# BV100011_ControlPower.net
KiCad netlist of a schematic drawn in Altium Designer
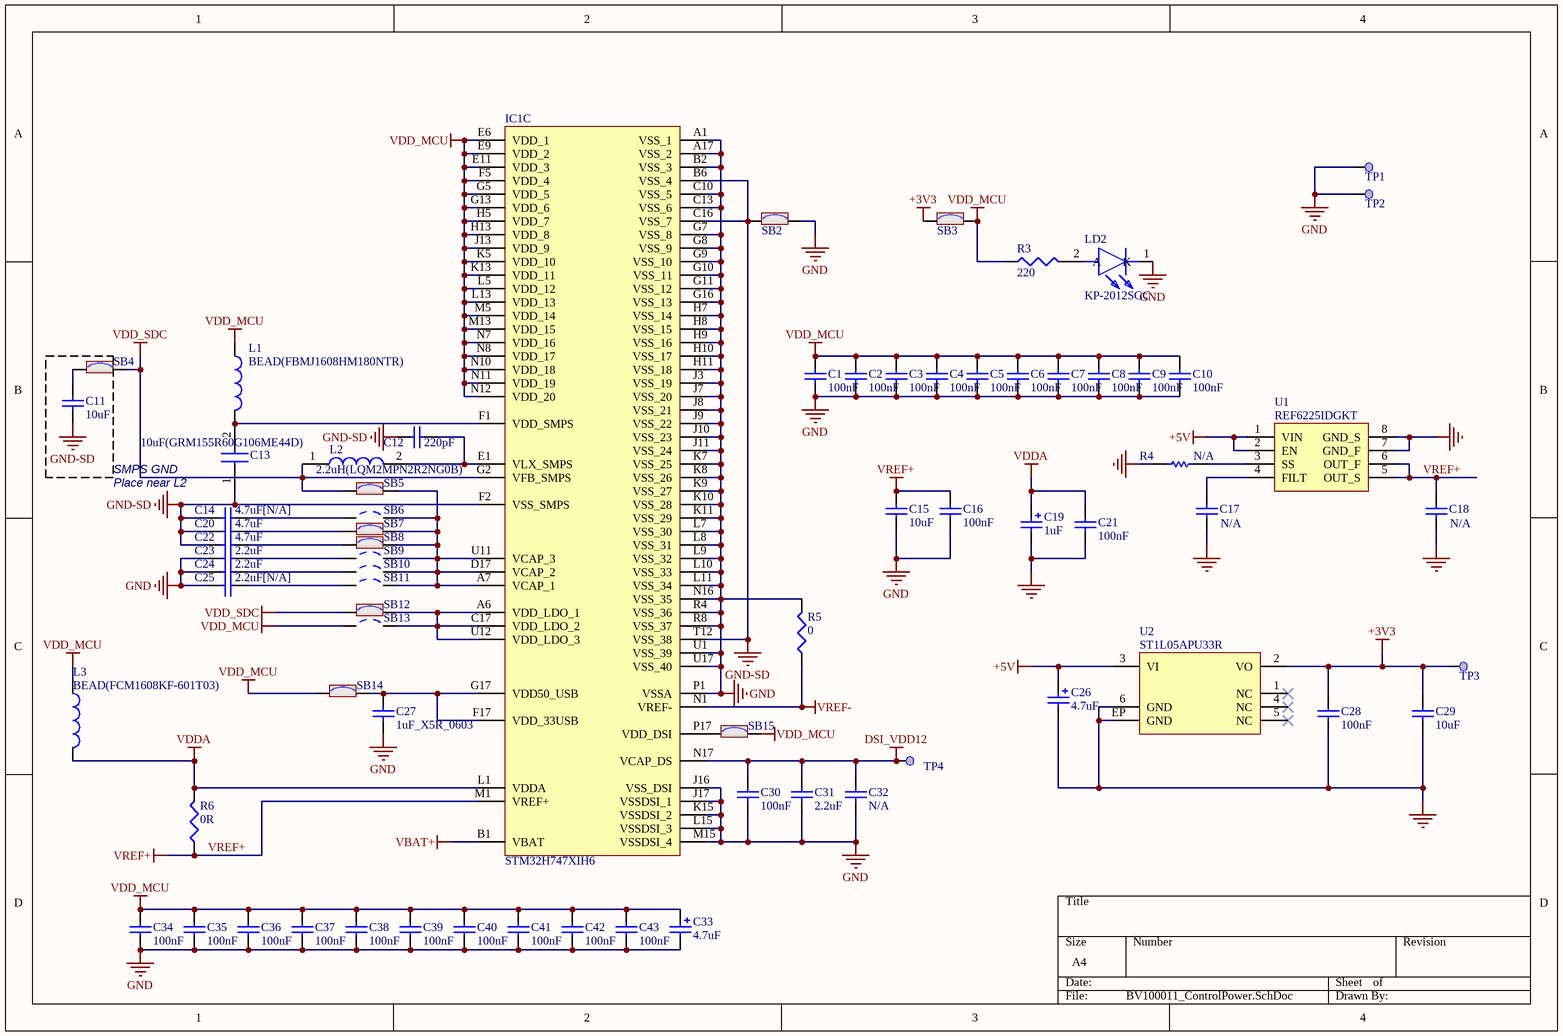
[diagram p0: BV100011_ControlPower.SchDoc]

(export (version "E")
  (design (tool "Eeschema 10.0.6"))
  (components
    (comp (ref "C1")
      (value "100nF")
      (footprint "C0402")
      (description "Capacitor (Semiconductor SIM Model)")
      (fields (field (name "PUBLISHER") "Altium Limited"))
      (libsource (lib "Miscellaneous Devices") (part "Cap Semi"))
    )
    (comp (ref "C2")
      (value "100nF")
      (footprint "C0402")
      (description "Capacitor (Semiconductor SIM Model)")
      (fields (field (name "PUBLISHER") "Altium Limited"))
      (libsource (lib "Miscellaneous Devices") (part "Cap Semi"))
    )
    (comp (ref "C3")
      (value "100nF")
      (footprint "C0402")
      (description "Capacitor (Semiconductor SIM Model)")
      (fields (field (name "PUBLISHER") "Altium Limited"))
      (libsource (lib "Miscellaneous Devices") (part "Cap Semi"))
    )
    (comp (ref "C4")
      (value "100nF")
      (footprint "C0402")
      (description "Capacitor (Semiconductor SIM Model)")
      (fields (field (name "PUBLISHER") "Altium Limited"))
      (libsource (lib "Miscellaneous Devices") (part "Cap Semi"))
    )
    (comp (ref "C5")
      (value "100nF")
      (footprint "C0402")
      (description "Capacitor (Semiconductor SIM Model)")
      (fields (field (name "PUBLISHER") "Altium Limited"))
      (libsource (lib "Miscellaneous Devices") (part "Cap Semi"))
    )
    (comp (ref "C6")
      (value "100nF")
      (footprint "C0402")
      (description "Capacitor (Semiconductor SIM Model)")
      (fields (field (name "PUBLISHER") "Altium Limited"))
      (libsource (lib "Miscellaneous Devices") (part "Cap Semi"))
    )
    (comp (ref "C7")
      (value "100nF")
      (footprint "C0402")
      (description "Capacitor (Semiconductor SIM Model)")
      (fields (field (name "PUBLISHER") "Altium Limited"))
      (libsource (lib "Miscellaneous Devices") (part "Cap Semi"))
    )
    (comp (ref "C8")
      (value "100nF")
      (footprint "C0402")
      (description "Capacitor (Semiconductor SIM Model)")
      (fields (field (name "PUBLISHER") "Altium Limited"))
      (libsource (lib "Miscellaneous Devices") (part "Cap Semi"))
    )
    (comp (ref "C9")
      (value "100nF")
      (footprint "C0402")
      (description "Capacitor (Semiconductor SIM Model)")
      (fields (field (name "PUBLISHER") "Altium Limited"))
      (libsource (lib "Miscellaneous Devices") (part "Cap Semi"))
    )
    (comp (ref "C10")
      (value "100nF")
      (footprint "C0402")
      (description "Capacitor (Semiconductor SIM Model)")
      (fields (field (name "PUBLISHER") "Altium Limited"))
      (libsource (lib "Miscellaneous Devices") (part "Cap Semi"))
    )
    (comp (ref "C11")
      (value "10uF")
      (footprint "C0603")
      (description "Capacitor (Semiconductor SIM Model)")
      (fields (field (name "PUBLISHER") "Altium Limited"))
      (libsource (lib "Miscellaneous Devices") (part "Cap Semi"))
    )
    (comp (ref "C12")
      (value "220pF")
      (footprint "C0402")
      (description "Capacitor (Semiconductor SIM Model)")
      (fields (field (name "PUBLISHER") "Altium Limited"))
      (libsource (lib "Miscellaneous Devices") (part "Cap Semi"))
    )
    (comp (ref "C13")
      (value "10uF(GRM155R60G106ME44D)")
      (footprint "C0402")
      (description "Capacitor")
      (fields
        (field (name "MANUFACTURER_PART_NUMBER") "GRM155R60G106ME44D")
        (field (name "MOUSER PART NUMBER") "81-GRM155R60G106ME4D")
      )
      (libsource (lib "*") (part "GRM155R60G106ME44D"))
    )
    (comp (ref "C14")
      (value "4.7uF[N/A]")
      (footprint "C0402")
      (description "Capacitor (Semiconductor SIM Model)")
      (fields (field (name "PUBLISHER") "Altium Limited"))
      (libsource (lib "Miscellaneous Devices") (part "Cap Semi"))
    )
    (comp (ref "C15")
      (value "10uF")
      (footprint "C0805")
      (description "Capacitor, MLCC, 10uF, 25V, X5R, 10%, 0805, T=0,85mm")
      (fields
        (field (name "INTERNAL_PART_NUMBER") "MCD-00014")
        (field (name "MANUFACTURER_PART_NUMBER") "CC0805KRX5R8BB106")
        (field (name "PROVIDED_BY") "Subcon")
      )
      (libsource (lib "MCD_PARTS_database") (part "Capacitor"))
    )
    (comp (ref "C16")
      (value "100nF")
      (footprint "C0402")
      (description "Capacitor (Semiconductor SIM Model)")
      (fields (field (name "PUBLISHER") "Altium Limited"))
      (libsource (lib "Miscellaneous Devices") (part "Cap Semi"))
    )
    (comp (ref "C17")
      (value "N/A")
      (footprint "C0603")
      (description "Capacitor, MLCC, 1uF, 16V, X5R, 10%, 0603, T=0,8mm")
      (fields
        (field (name "INTERNAL_PART_NUMBER") "MCD-00010")
        (field (name "MANUFACTURER_PART_NUMBER") "CC0603KRX5R7BB105")
        (field (name "PROVIDED_BY") "Subcon")
      )
      (libsource (lib "MCD_PARTS_database") (part "Capacitor"))
    )
    (comp (ref "C18")
      (value "N/A")
      (footprint "C1210")
      (description "Capacitor, MLCC, 22uF, 16V, 1210, X7R, 20%, T=2,5mm, ESR 2mohm@410KHz")
      (fields
        (field (name "INTERNAL_PART_NUMBER") "MCD-00614")
        (field (name "MANUFACTURER_PART_NUMBER") "GCM32ER71C226ME19")
        (field (name "PROVIDED_BY") "Subcon")
      )
      (libsource (lib "MCD_PARTS_database") (part "Capacitor"))
    )
    (comp (ref "C19")
      (value "1uF")
      (footprint "CPOL_VISHAY_TANTAL-595D_1407_H220")
      (description "Capacitor, Tantalum, 1uF, 35V, +/-10%, 595D case A")
      (fields
        (field (name "INTERNAL_PART_NUMBER") "MCD-00594")
        (field (name "MANUFACTURER_PART_NUMBER") "595D105X9035A2T")
        (field (name "PROVIDED_BY") "Subcon")
      )
      (libsource (lib "MCD_PARTS_database") (part "Cap_POL_TANA"))
    )
    (comp (ref "C20")
      (value "4.7uF")
      (footprint "C0402")
      (description "Capacitor (Semiconductor SIM Model)")
      (fields (field (name "PUBLISHER") "Altium Limited"))
      (libsource (lib "Miscellaneous Devices") (part "Cap Semi"))
    )
    (comp (ref "C21")
      (value "100nF")
      (footprint "C0402")
      (description "Capacitor, MLCC, 100nF, 16V, X7R, 10%, 0402, T=0,5mm")
      (fields
        (field (name "INTERNAL_PART_NUMBER") "MCD-00102")
        (field (name "MANUFACTURER_PART_NUMBER") "CC0402KRX7R7BB104")
        (field (name "PROVIDED_BY") "Subcon")
      )
      (libsource (lib "MCD_PARTS_database") (part "Capacitor"))
    )
    (comp (ref "C22")
      (value "4.7uF")
      (footprint "C0402")
      (description "Capacitor (Semiconductor SIM Model)")
      (fields (field (name "PUBLISHER") "Altium Limited"))
      (libsource (lib "Miscellaneous Devices") (part "Cap Semi"))
    )
    (comp (ref "C23")
      (value "2.2uF")
      (footprint "C0603")
      (description "Capacitor")
      (fields (field (name "PUBLISHER") "Altium Limited"))
      (libsource (lib "Miscellaneous Devices") (part "Cap"))
    )
    (comp (ref "C24")
      (value "2.2uF")
      (footprint "C0603")
      (description "Capacitor")
      (fields (field (name "PUBLISHER") "Altium Limited"))
      (libsource (lib "Miscellaneous Devices") (part "Cap"))
    )
    (comp (ref "C25")
      (value "2.2uF[N/A]")
      (footprint "C0603")
      (description "Capacitor")
      (fields (field (name "PUBLISHER") "Altium Limited"))
      (libsource (lib "Miscellaneous Devices") (part "Cap"))
    )
    (comp (ref "C26")
      (value "4.7uF")
      (footprint "CPOL_VISHAY_TANTAL-595D_1407_H220")
      (description "Capacitor, Tantalum, 4.7uF, 16V, +/-10%, 595D case A")
      (fields
        (field (name "INTERNAL_PART_NUMBER") "MCD-00595")
        (field (name "MANUFACTURER_PART_NUMBER") "595D475X9016A2T")
        (field (name "PROVIDED_BY") "Subcon")
      )
      (libsource (lib "MCD_PARTS_database") (part "Cap_POL_TANA"))
    )
    (comp (ref "C27")
      (value "1uF_X5R_0603")
      (footprint "C0603")
      (description "Capacitor (Semiconductor SIM Model)")
      (fields (field (name "PUBLISHER") "Altium Limited"))
      (libsource (lib "Miscellaneous Devices") (part "Cap Semi"))
    )
    (comp (ref "C28")
      (value "100nF")
      (footprint "C0402")
      (description "Capacitor, MLCC, 100nF, 16V, X7R, 10%, 0402, T=0,5mm")
      (fields
        (field (name "INTERNAL_PART_NUMBER") "MCD-00102")
        (field (name "MANUFACTURER_PART_NUMBER") "CC0402KRX7R7BB104")
        (field (name "PROVIDED_BY") "Subcon")
      )
      (libsource (lib "MCD_PARTS_database") (part "Capacitor"))
    )
    (comp (ref "C29")
      (value "10uF")
      (footprint "C0805")
      (description "Capacitor, MLCC, 10uF, 25V, X5R, 10%, 0805, T=0,85mm")
      (fields
        (field (name "INTERNAL_PART_NUMBER") "MCD-00014")
        (field (name "MANUFACTURER_PART_NUMBER") "CC0805KRX5R8BB106")
        (field (name "PROVIDED_BY") "Subcon")
      )
      (libsource (lib "MCD_PARTS_database") (part "Capacitor"))
    )
    (comp (ref "C30")
      (value "100nF")
      (footprint "C0402")
      (description "Capacitor (Semiconductor SIM Model)")
      (fields (field (name "PUBLISHER") "Altium Limited"))
      (libsource (lib "Miscellaneous Devices") (part "Cap Semi"))
    )
    (comp (ref "C31")
      (value "2.2uF")
      (footprint "C0603")
      (description "Capacitor (Semiconductor SIM Model)")
      (fields (field (name "PUBLISHER") "Altium Limited"))
      (libsource (lib "Miscellaneous Devices") (part "Cap Semi"))
    )
    (comp (ref "C32")
      (value "N/A")
      (footprint "C1206")
      (description "Capacitor (Semiconductor SIM Model)")
      (fields (field (name "PUBLISHER") "Altium Limited"))
      (libsource (lib "Miscellaneous Devices") (part "Cap Semi"))
    )
    (comp (ref "C33")
      (value "4.7uF")
      (footprint "CPOL_VISHAY_TANTAL-595D_1407_H220")
      (description "Capacitor, Tantalum, 4.7uF, 16V, +/-10%, 595D case A")
      (fields
        (field (name "INTERNAL_PART_NUMBER") "MCD-00595")
        (field (name "MANUFACTURER_PART_NUMBER") "595D475X9016A2T")
        (field (name "PROVIDED_BY") "Subcon")
      )
      (libsource (lib "MCD_PARTS_database") (part "Cap_POL_TANA"))
    )
    (comp (ref "C34")
      (value "100nF")
      (footprint "C0402")
      (description "Capacitor (Semiconductor SIM Model)")
      (fields (field (name "PUBLISHER") "Altium Limited"))
      (libsource (lib "Miscellaneous Devices") (part "Cap Semi"))
    )
    (comp (ref "C35")
      (value "100nF")
      (footprint "C0402")
      (description "Capacitor (Semiconductor SIM Model)")
      (fields (field (name "PUBLISHER") "Altium Limited"))
      (libsource (lib "Miscellaneous Devices") (part "Cap Semi"))
    )
    (comp (ref "C36")
      (value "100nF")
      (footprint "C0402")
      (description "Capacitor (Semiconductor SIM Model)")
      (fields (field (name "PUBLISHER") "Altium Limited"))
      (libsource (lib "Miscellaneous Devices") (part "Cap Semi"))
    )
    (comp (ref "C37")
      (value "100nF")
      (footprint "C0402")
      (description "Capacitor (Semiconductor SIM Model)")
      (fields (field (name "PUBLISHER") "Altium Limited"))
      (libsource (lib "Miscellaneous Devices") (part "Cap Semi"))
    )
    (comp (ref "C38")
      (value "100nF")
      (footprint "C0402")
      (description "Capacitor (Semiconductor SIM Model)")
      (fields (field (name "PUBLISHER") "Altium Limited"))
      (libsource (lib "Miscellaneous Devices") (part "Cap Semi"))
    )
    (comp (ref "C39")
      (value "100nF")
      (footprint "C0402")
      (description "Capacitor (Semiconductor SIM Model)")
      (fields (field (name "PUBLISHER") "Altium Limited"))
      (libsource (lib "Miscellaneous Devices") (part "Cap Semi"))
    )
    (comp (ref "C40")
      (value "100nF")
      (footprint "C0402")
      (description "Capacitor (Semiconductor SIM Model)")
      (fields (field (name "PUBLISHER") "Altium Limited"))
      (libsource (lib "Miscellaneous Devices") (part "Cap Semi"))
    )
    (comp (ref "C41")
      (value "100nF")
      (footprint "C0402")
      (description "Capacitor (Semiconductor SIM Model)")
      (fields (field (name "PUBLISHER") "Altium Limited"))
      (libsource (lib "Miscellaneous Devices") (part "Cap Semi"))
    )
    (comp (ref "C42")
      (value "100nF")
      (footprint "C0402")
      (description "Capacitor (Semiconductor SIM Model)")
      (fields (field (name "PUBLISHER") "Altium Limited"))
      (libsource (lib "Miscellaneous Devices") (part "Cap Semi"))
    )
    (comp (ref "C43")
      (value "100nF")
      (footprint "C0402")
      (description "Capacitor (Semiconductor SIM Model)")
      (fields (field (name "PUBLISHER") "Altium Limited"))
      (libsource (lib "Miscellaneous Devices") (part "Cap Semi"))
    )
    (comp (ref "IC1")
      (value "STM32H747XIH6")
      (footprint "BGA265C80P17X17_1400X1400X110")
      (description "Integrated Circuit")
      (fields (field (name "MOUSER PART NUMBER") "511-STM32H747XIH6"))
      (libsource (lib "STM32H747XIH6") (part "STM32H747XIH6"))
    )
    (comp (ref "L1")
      (value "BEAD(FBMJ1608HM180NTR)")
      (footprint "L0603")
      (description "Inductor")
      (fields (field (name "PUBLISHER") "Altium Limited"))
      (libsource (lib "Miscellaneous Devices") (part "Inductor"))
    )
    (comp (ref "L2")
      (value "2.2uH(LQM2MPN2R2NG0B)")
      (footprint "IND_2016_MURATA_LQM2MPN2R2NG0")
      (description "Inductor")
      (fields (field (name "MANUFACTURER_PART_NUMBER") "LQM2MPN2R2NG0B"))
      (libsource (lib "*") (part "LQM2MPN2R2NG0B"))
    )
    (comp (ref "L3")
      (value "BEAD(FCM1608KF-601T03)")
      (footprint "L0603")
      (description "Inductor")
      (fields (field (name "PUBLISHER") "Altium Limited"))
      (libsource (lib "Miscellaneous Devices") (part "Inductor"))
    )
    (comp (ref "LD2")
      (value "KP-2012SGC")
      (footprint "SamacSys:LEDC2012X110N")
      (description "LED")
      (fields (field (name "RS PART NUMBER") "4663807P"))
      (libsource (lib "*") (part "KP-2012SGC"))
    )
    (comp (ref "R3")
      (value "220")
      (footprint "R0603")
      (description "Resistor")
      (fields (field (name "PUBLISHER") "Altium Limited"))
      (libsource (lib "Miscellaneous Devices") (part "Res3"))
    )
    (comp (ref "R4")
      (value "N/A")
      (footprint "R0402")
      (description "Resistor,120K,0402,1%,1/16W")
      (fields
        (field (name "INTERNAL_PART_NUMBER") "MCD-00166")
        (field (name "MANUFACTURER_PART_NUMBER") "RC0402FR-07120KL")
        (field (name "PROVIDED_BY") "Subcon")
      )
      (libsource (lib "MCD_PARTS_database") (part "Resistor"))
    )
    (comp (ref "R5")
      (value "0")
      (footprint "R0603")
      (description "Resistor")
      (fields (field (name "PUBLISHER") "Altium Limited"))
      (libsource (lib "Miscellaneous Devices") (part "Res3"))
    )
    (comp (ref "R6")
      (value "0R")
      (footprint "R0603")
      (description "Resistor")
      (fields (field (name "PUBLISHER") "Altium Limited"))
      (libsource (lib "Miscellaneous Devices") (part "Res3"))
    )
    (comp (ref "SB2")
      (value "SB_ON")
      (footprint "SB_0603")
      (description "Solder Bridge ON")
      (fields
        (field (name "INTERNAL_PART_NUMBER") "MCD-00071")
        (field (name "MANUFACTURER_PART_NUMBER") "RC0603JR-070RL")
        (field (name "PROVIDED_BY") "SUBCO")
      )
      (libsource (lib "MB1364") (part "MCD-00071"))
    )
    (comp (ref "SB3")
      (value "SB_ON")
      (footprint "SB_0603")
      (description "Solder Bridge ON")
      (fields
        (field (name "INTERNAL_PART_NUMBER") "MCD-00071")
        (field (name "MANUFACTURER_PART_NUMBER") "RC0603JR-070RL")
        (field (name "PROVIDED_BY") "SUBCO")
      )
      (libsource (lib "MB1364") (part "MCD-00071"))
    )
    (comp (ref "SB4")
      (value "Solder Bridge ON")
      (footprint "SB_0603")
      (libsource (lib "MCD_TOOLS") (part "SB_ON"))
    )
    (comp (ref "SB5")
      (value "Solder Bridge ON")
      (footprint "SB_0603")
      (libsource (lib "MCD_TOOLS") (part "SB_ON"))
    )
    (comp (ref "SB6")
      (value "Solder Bridge OFF")
      (footprint "SB_0603")
      (libsource (lib "MCD_TOOLS") (part "SB_OFF"))
    )
    (comp (ref "SB7")
      (value "Solder Bridge ON")
      (footprint "SB_0603")
      (libsource (lib "MCD_TOOLS") (part "SB_ON"))
    )
    (comp (ref "SB8")
      (value "Solder Bridge ON")
      (footprint "SB_0603")
      (libsource (lib "MCD_TOOLS") (part "SB_ON"))
    )
    (comp (ref "SB9")
      (value "Solder Bridge OFF")
      (footprint "SB_0603")
      (libsource (lib "MCD_TOOLS") (part "SB_OFF"))
    )
    (comp (ref "SB10")
      (value "Solder Bridge OFF")
      (footprint "SB_0603")
      (libsource (lib "MCD_TOOLS") (part "SB_OFF"))
    )
    (comp (ref "SB11")
      (value "Solder Bridge OFF")
      (footprint "SB_0603")
      (libsource (lib "MCD_TOOLS") (part "SB_OFF"))
    )
    (comp (ref "SB12")
      (value "Solder Bridge ON")
      (footprint "SB_0603")
      (libsource (lib "MCD_TOOLS") (part "SB_ON"))
    )
    (comp (ref "SB13")
      (value "Solder Bridge OFF")
      (footprint "SB_0603")
      (libsource (lib "MCD_TOOLS") (part "SB_OFF"))
    )
    (comp (ref "SB14")
      (value "Solder Bridge ON")
      (footprint "SB_0603")
      (libsource (lib "MCD_TOOLS") (part "SB_ON"))
    )
    (comp (ref "SB15")
      (value "Solder Bridge ON")
      (footprint "SB_0603")
      (libsource (lib "MCD_TOOLS") (part "SB_ON"))
    )
    (comp (ref "TP1")
      (value "Test Point")
      (footprint "TP_SMD_0-3MM")
      (description "Test Point 0.3mm")
      (fields (field (name "INTERNAL_PART_NUMBER") "MCD-00630"))
      (libsource (lib "MCD_PARTS_database") (part "Test Point"))
    )
    (comp (ref "TP2")
      (value "Test Point")
      (footprint "TP_SMD_0-3MM")
      (description "Test Point 0.3mm")
      (fields (field (name "INTERNAL_PART_NUMBER") "MCD-00630"))
      (libsource (lib "MCD_PARTS_database") (part "Test Point"))
    )
    (comp (ref "TP3")
      (value "Test Point")
      (footprint "TP_SMD_0-3MM")
      (description "Test Point 0.3mm")
      (fields (field (name "INTERNAL_PART_NUMBER") "MCD-00630"))
      (libsource (lib "MCD_PARTS_database") (part "Test Point"))
    )
    (comp (ref "TP4")
      (value "Test Point")
      (footprint "TP_SMD_0-3MM")
      (description "Test Point 0.3mm")
      (fields (field (name "INTERNAL_PART_NUMBER") "MCD-00630"))
      (libsource (lib "MCD_PARTS_database") (part "Test Point"))
    )
    (comp (ref "U1")
      (value "REF6225IDGKT")
      (footprint "ICC_VSSOP8_DGK_S-PDSO-G8_3X3_P065")
      (description "IC VREF SERIES 2.5V 8VSSOP")
      (fields
        (field (name "INTERNAL_PART_NUMBER") "MCD-01138")
        (field (name "MANUFACTURER") "TI")
        (field (name "PROVIDED_BY") "Subcon")
      )
      (libsource (lib "MCD_PARTS_database") (part "REF6225IDGKT"))
    )
    (comp (ref "U2")
      (value "ST1L05APU33R")
      (footprint "ICC_DFN6-EPAD_3X3_P095")
      (description "IC REG LDO 3.3V 1.3A 6DFN")
      (fields
        (field (name "INTERNAL_PART_NUMBER") "MCD-01127")
        (field (name "MANUFACTURER") "STMICROELECTRONICS")
        (field (name "PROVIDED_BY") "Subcon")
      )
      (libsource (lib "MCD_PARTS_database") (part "ST1L05APU33R"))
    )
  )
  (nets
    (net (code "1") (name "+3V3") (class "Default")
      (node (ref "C28") (pin "1") (pinfunction "1_1") (pintype "passive"))
      (node (ref "C29") (pin "2") (pinfunction "2_2") (pintype "passive"))
      (node (ref "SB3") (pin "1") (pinfunction "1_1") (pintype "passive"))
      (node (ref "TP3") (pin "1") (pinfunction "1_1") (pintype "passive"))
      (node (ref "U2") (pin "2") (pinfunction "VO_2") (pintype "passive"))
    )
    (net (code "2") (name "+5V") (class "Default")
      (node (ref "C26") (pin "1") (pinfunction "1_1") (pintype "passive"))
      (node (ref "U1") (pin "1") (pinfunction "VIN_1") (pintype "passive"))
      (node (ref "U1") (pin "2") (pinfunction "EN_2") (pintype "passive"))
      (node (ref "U2") (pin "3") (pinfunction "VI_3") (pintype "passive"))
    )
    (net (code "3") (name "DSI_VDD12") (class "Default")
      (node (ref "C30") (pin "2") (pinfunction "2_2") (pintype "passive"))
      (node (ref "C31") (pin "2") (pinfunction "2_2") (pintype "passive"))
      (node (ref "C32") (pin "2") (pinfunction "2_2") (pintype "passive"))
      (node (ref "IC1") (pin "N17") (pinfunction "VCAP_DS_N17") (pintype "passive"))
      (node (ref "TP4") (pin "1") (pinfunction "1_1") (pintype "passive"))
    )
    (net (code "4") (name "GND") (class "Default")
      (node (ref "C1") (pin "1") (pinfunction "1_1") (pintype "passive"))
      (node (ref "C10") (pin "1") (pinfunction "1_1") (pintype "passive"))
      (node (ref "C15") (pin "1") (pinfunction "1_1") (pintype "passive"))
      (node (ref "C16") (pin "1") (pinfunction "1_1") (pintype "passive"))
      (node (ref "C17") (pin "1") (pinfunction "1_1") (pintype "passive"))
      (node (ref "C18") (pin "1") (pinfunction "1_1") (pintype "passive"))
      (node (ref "C19") (pin "2") (pinfunction "2_2") (pintype "passive"))
      (node (ref "C2") (pin "1") (pinfunction "1_1") (pintype "passive"))
      (node (ref "C21") (pin "1") (pinfunction "1_1") (pintype "passive"))
      (node (ref "C23") (pin "1") (pinfunction "1_1") (pintype "passive"))
      (node (ref "C24") (pin "1") (pinfunction "1_1") (pintype "passive"))
      (node (ref "C25") (pin "1") (pinfunction "1_1") (pintype "passive"))
      (node (ref "C26") (pin "2") (pinfunction "2_2") (pintype "passive"))
      (node (ref "C27") (pin "1") (pinfunction "1_1") (pintype "passive"))
      (node (ref "C28") (pin "2") (pinfunction "2_2") (pintype "passive"))
      (node (ref "C29") (pin "1") (pinfunction "1_1") (pintype "passive"))
      (node (ref "C3") (pin "1") (pinfunction "1_1") (pintype "passive"))
      (node (ref "C30") (pin "1") (pinfunction "1_1") (pintype "passive"))
      (node (ref "C31") (pin "1") (pinfunction "1_1") (pintype "passive"))
      (node (ref "C32") (pin "1") (pinfunction "1_1") (pintype "passive"))
      (node (ref "C33") (pin "2") (pinfunction "2_2") (pintype "passive"))
      (node (ref "C34") (pin "1") (pinfunction "1_1") (pintype "passive"))
      (node (ref "C35") (pin "1") (pinfunction "1_1") (pintype "passive"))
      (node (ref "C36") (pin "1") (pinfunction "1_1") (pintype "passive"))
      (node (ref "C37") (pin "1") (pinfunction "1_1") (pintype "passive"))
      (node (ref "C38") (pin "1") (pinfunction "1_1") (pintype "passive"))
      (node (ref "C39") (pin "1") (pinfunction "1_1") (pintype "passive"))
      (node (ref "C4") (pin "1") (pinfunction "1_1") (pintype "passive"))
      (node (ref "C40") (pin "1") (pinfunction "1_1") (pintype "passive"))
      (node (ref "C41") (pin "1") (pinfunction "1_1") (pintype "passive"))
      (node (ref "C42") (pin "1") (pinfunction "1_1") (pintype "passive"))
      (node (ref "C43") (pin "1") (pinfunction "1_1") (pintype "passive"))
      (node (ref "C5") (pin "1") (pinfunction "1_1") (pintype "passive"))
      (node (ref "C6") (pin "1") (pinfunction "1_1") (pintype "passive"))
      (node (ref "C7") (pin "1") (pinfunction "1_1") (pintype "passive"))
      (node (ref "C8") (pin "1") (pinfunction "1_1") (pintype "passive"))
      (node (ref "C9") (pin "1") (pinfunction "1_1") (pintype "passive"))
      (node (ref "IC1") (pin "A1") (pinfunction "VSS_1_A1") (pintype "passive"))
      (node (ref "IC1") (pin "A17") (pinfunction "VSS_2_A17") (pintype "passive"))
      (node (ref "IC1") (pin "B2") (pinfunction "VSS_3_B2") (pintype "passive"))
      (node (ref "IC1") (pin "C10") (pinfunction "VSS_5_C10") (pintype "passive"))
      (node (ref "IC1") (pin "C13") (pinfunction "VSS_6_C13") (pintype "passive"))
      (node (ref "IC1") (pin "G10") (pinfunction "VSS_11_G10") (pintype "passive"))
      (node (ref "IC1") (pin "G11") (pinfunction "VSS_12_G11") (pintype "passive"))
      (node (ref "IC1") (pin "G16") (pinfunction "VSS_13_G16") (pintype "passive"))
      (node (ref "IC1") (pin "G7") (pinfunction "VSS_8_G7") (pintype "passive"))
      (node (ref "IC1") (pin "G8") (pinfunction "VSS_9_G8") (pintype "passive"))
      (node (ref "IC1") (pin "G9") (pinfunction "VSS_10_G9") (pintype "passive"))
      (node (ref "IC1") (pin "H10") (pinfunction "VSS_17_H10") (pintype "passive"))
      (node (ref "IC1") (pin "H11") (pinfunction "VSS_18_H11") (pintype "passive"))
      (node (ref "IC1") (pin "H7") (pinfunction "VSS_14_H7") (pintype "passive"))
      (node (ref "IC1") (pin "H8") (pinfunction "VSS_15_H8") (pintype "passive"))
      (node (ref "IC1") (pin "H9") (pinfunction "VSS_16_H9") (pintype "passive"))
      (node (ref "IC1") (pin "J10") (pinfunction "VSS_23_J10") (pintype "passive"))
      (node (ref "IC1") (pin "J11") (pinfunction "VSS_24_J11") (pintype "passive"))
      (node (ref "IC1") (pin "J16") (pinfunction "VSS_DSI_J16") (pintype "passive"))
      (node (ref "IC1") (pin "J17") (pinfunction "VSSDSI_1_J17") (pintype "passive"))
      (node (ref "IC1") (pin "J3") (pinfunction "VSS_19_J3") (pintype "passive"))
      (node (ref "IC1") (pin "J7") (pinfunction "VSS_20_J7") (pintype "passive"))
      (node (ref "IC1") (pin "J8") (pinfunction "VSS_21_J8") (pintype "passive"))
      (node (ref "IC1") (pin "J9") (pinfunction "VSS_22_J9") (pintype "passive"))
      (node (ref "IC1") (pin "K10") (pinfunction "VSS_28_K10") (pintype "passive"))
      (node (ref "IC1") (pin "K11") (pinfunction "VSS_29_K11") (pintype "passive"))
      (node (ref "IC1") (pin "K15") (pinfunction "VSSDSI_2_K15") (pintype "passive"))
      (node (ref "IC1") (pin "K7") (pinfunction "VSS_25_K7") (pintype "passive"))
      (node (ref "IC1") (pin "K8") (pinfunction "VSS_26_K8") (pintype "passive"))
      (node (ref "IC1") (pin "K9") (pinfunction "VSS_27_K9") (pintype "passive"))
      (node (ref "IC1") (pin "L10") (pinfunction "VSS_33_L10") (pintype "passive"))
      (node (ref "IC1") (pin "L11") (pinfunction "VSS_34_L11") (pintype "passive"))
      (node (ref "IC1") (pin "L15") (pinfunction "VSSDSI_3_L15") (pintype "passive"))
      (node (ref "IC1") (pin "L7") (pinfunction "VSS_30_L7") (pintype "passive"))
      (node (ref "IC1") (pin "L8") (pinfunction "VSS_31_L8") (pintype "passive"))
      (node (ref "IC1") (pin "L9") (pinfunction "VSS_32_L9") (pintype "passive"))
      (node (ref "IC1") (pin "M15") (pinfunction "VSSDSI_4_M15") (pintype "passive"))
      (node (ref "IC1") (pin "N16") (pinfunction "VSS_35_N16") (pintype "passive"))
      (node (ref "IC1") (pin "P1") (pinfunction "VSSA_P1") (pintype "passive"))
      (node (ref "IC1") (pin "R4") (pinfunction "VSS_36_R4") (pintype "passive"))
      (node (ref "IC1") (pin "R8") (pinfunction "VSS_37_R8") (pintype "passive"))
      (node (ref "IC1") (pin "U1") (pinfunction "VSS_39_U1") (pintype "passive"))
      (node (ref "IC1") (pin "U17") (pinfunction "VSS_40_U17") (pintype "passive"))
      (node (ref "LD2") (pin "1") (pinfunction "K_1") (pintype "passive"))
      (node (ref "R4") (pin "1") (pinfunction "1_1") (pintype "passive"))
      (node (ref "R5") (pin "2") (pinfunction "2_2") (pintype "passive"))
      (node (ref "SB2") (pin "2") (pinfunction "2_2") (pintype "passive"))
      (node (ref "TP1") (pin "1") (pinfunction "1_1") (pintype "passive"))
      (node (ref "TP2") (pin "1") (pinfunction "1_1") (pintype "passive"))
      (node (ref "U1") (pin "7") (pinfunction "GND_F_7") (pintype "passive"))
      (node (ref "U1") (pin "8") (pinfunction "GND_S_8") (pintype "passive"))
      (node (ref "U2") (pin "6") (pinfunction "GND_6") (pintype "passive"))
      (node (ref "U2") (pin "EP") (pinfunction "GND_EP") (pintype "passive"))
    )
    (net (code "5") (name "GND-SD") (class "Default")
      (node (ref "C11") (pin "1") (pinfunction "1_1") (pintype "passive"))
      (node (ref "C12") (pin "1") (pinfunction "1_1") (pintype "passive"))
      (node (ref "C13") (pin "1") (pinfunction "1_1") (pintype "passive"))
      (node (ref "C14") (pin "1") (pinfunction "1_1") (pintype "passive"))
      (node (ref "C20") (pin "1") (pinfunction "1_1") (pintype "passive"))
      (node (ref "C22") (pin "1") (pinfunction "1_1") (pintype "passive"))
      (node (ref "IC1") (pin "B6") (pinfunction "VSS_4_B6") (pintype "passive"))
      (node (ref "IC1") (pin "C16") (pinfunction "VSS_7_C16") (pintype "passive"))
      (node (ref "IC1") (pin "F2") (pinfunction "VSS_SMPS_F2") (pintype "passive"))
      (node (ref "IC1") (pin "T12") (pinfunction "VSS_38_T12") (pintype "passive"))
      (node (ref "SB2") (pin "1") (pinfunction "1_1") (pintype "passive"))
    )
    (net (code "6") (name "Net-(C11-Pad2)") (class "Default")
      (node (ref "C11") (pin "2") (pinfunction "2_2") (pintype "passive"))
      (node (ref "SB4") (pin "1") (pinfunction "1_1") (pintype "passive"))
    )
    (net (code "7") (name "Net-(C14-Pad2)") (class "Default")
      (node (ref "C14") (pin "2") (pinfunction "2_2") (pintype "passive"))
      (node (ref "SB6") (pin "1") (pinfunction "1_1") (pintype "passive"))
    )
    (net (code "8") (name "Net-(C20-Pad2)") (class "Default")
      (node (ref "C20") (pin "2") (pinfunction "2_2") (pintype "passive"))
      (node (ref "SB7") (pin "1") (pinfunction "1_1") (pintype "passive"))
    )
    (net (code "9") (name "Net-(C22-Pad2)") (class "Default")
      (node (ref "C22") (pin "2") (pinfunction "2_2") (pintype "passive"))
      (node (ref "SB8") (pin "1") (pinfunction "1_1") (pintype "passive"))
    )
    (net (code "10") (name "Net-(C23-Pad2)") (class "Default")
      (node (ref "C23") (pin "2") (pinfunction "2_2") (pintype "passive"))
      (node (ref "SB9") (pin "1") (pinfunction "1_1") (pintype "passive"))
    )
    (net (code "11") (name "Net-(C24-Pad2)") (class "Default")
      (node (ref "C24") (pin "2") (pinfunction "2_2") (pintype "passive"))
      (node (ref "SB10") (pin "1") (pinfunction "1_1") (pintype "passive"))
    )
    (net (code "12") (name "Net-(C25-Pad2)") (class "Default")
      (node (ref "C25") (pin "2") (pinfunction "2_2") (pintype "passive"))
      (node (ref "SB11") (pin "1") (pinfunction "1_1") (pintype "passive"))
    )
    (net (code "13") (name "Net-(IC1C-VCAP_1)") (class "Default")
      (node (ref "IC1") (pin "A7") (pinfunction "VCAP_1_A7") (pintype "passive"))
      (node (ref "IC1") (pin "D17") (pinfunction "VCAP_2_D17") (pintype "passive"))
      (node (ref "IC1") (pin "U11") (pinfunction "VCAP_3_U11") (pintype "passive"))
      (node (ref "SB10") (pin "2") (pinfunction "2_2") (pintype "passive"))
      (node (ref "SB11") (pin "2") (pinfunction "2_2") (pintype "passive"))
      (node (ref "SB5") (pin "2") (pinfunction "2_2") (pintype "passive"))
      (node (ref "SB6") (pin "2") (pinfunction "2_2") (pintype "passive"))
      (node (ref "SB7") (pin "2") (pinfunction "2_2") (pintype "passive"))
      (node (ref "SB8") (pin "2") (pinfunction "2_2") (pintype "passive"))
      (node (ref "SB9") (pin "2") (pinfunction "2_2") (pintype "passive"))
    )
    (net (code "14") (name "Net-(IC1C-VDD50_USB)") (class "Default")
      (node (ref "C27") (pin "2") (pinfunction "2_2") (pintype "passive"))
      (node (ref "IC1") (pin "F17") (pinfunction "VDD_33USB_F17") (pintype "passive"))
      (node (ref "IC1") (pin "G17") (pinfunction "VDD50_USB_G17") (pintype "passive"))
      (node (ref "SB14") (pin "2") (pinfunction "2_2") (pintype "passive"))
    )
    (net (code "15") (name "Net-(IC1C-VDD_DSI)") (class "Default")
      (node (ref "IC1") (pin "P17") (pinfunction "VDD_DSI_P17") (pintype "passive"))
      (node (ref "SB15") (pin "1") (pinfunction "1_1") (pintype "passive"))
    )
    (net (code "16") (name "Net-(IC1C-VDD_LDO_1)") (class "Default")
      (node (ref "IC1") (pin "A6") (pinfunction "VDD_LDO_1_A6") (pintype "passive"))
      (node (ref "IC1") (pin "C17") (pinfunction "VDD_LDO_2_C17") (pintype "passive"))
      (node (ref "IC1") (pin "U12") (pinfunction "VDD_LDO_3_U12") (pintype "passive"))
      (node (ref "SB12") (pin "2") (pinfunction "2_2") (pintype "passive"))
      (node (ref "SB13") (pin "2") (pinfunction "2_2") (pintype "passive"))
    )
    (net (code "17") (name "Net-(IC1C-VDD_SMPS)") (class "Default")
      (node (ref "C13") (pin "2") (pinfunction "2_2") (pintype "passive"))
      (node (ref "IC1") (pin "F1") (pinfunction "VDD_SMPS_F1") (pintype "passive"))
      (node (ref "L1") (pin "2") (pinfunction "2_2") (pintype "passive"))
    )
    (net (code "18") (name "Net-(IC1C-VLX_SMPS)") (class "Default")
      (node (ref "C12") (pin "2") (pinfunction "2_2") (pintype "passive"))
      (node (ref "IC1") (pin "E1") (pinfunction "VLX_SMPS_E1") (pintype "passive"))
      (node (ref "L2") (pin "2") (pinfunction "2_2") (pintype "passive"))
    )
    (net (code "19") (name "Net-(LD2-A)") (class "Default")
      (node (ref "LD2") (pin "2") (pinfunction "A_2") (pintype "passive"))
      (node (ref "R3") (pin "2") (pinfunction "2_2") (pintype "passive"))
    )
    (net (code "20") (name "Net-(U1-FILT)") (class "Default")
      (node (ref "C17") (pin "2") (pinfunction "2_2") (pintype "passive"))
      (node (ref "U1") (pin "4") (pinfunction "FILT_4") (pintype "passive"))
    )
    (net (code "21") (name "Net-(U1-SS)") (class "Default")
      (node (ref "R4") (pin "2") (pinfunction "2_2") (pintype "passive"))
      (node (ref "U1") (pin "3") (pinfunction "SS_3") (pintype "passive"))
    )
    (net (code "22") (name "VBAT+") (class "Default")
      (node (ref "IC1") (pin "B1") (pinfunction "VBAT_B1") (pintype "passive"))
    )
    (net (code "23") (name "VDDA") (class "Default")
      (node (ref "C19") (pin "1") (pinfunction "1_1") (pintype "passive"))
      (node (ref "C21") (pin "2") (pinfunction "2_2") (pintype "passive"))
      (node (ref "IC1") (pin "L1") (pinfunction "VDDA_L1") (pintype "passive"))
      (node (ref "L3") (pin "2") (pinfunction "2_2") (pintype "passive"))
      (node (ref "R6") (pin "2") (pinfunction "2_2") (pintype "passive"))
    )
    (net (code "24") (name "VDD_MCU") (class "Default")
      (node (ref "C1") (pin "2") (pinfunction "2_2") (pintype "passive"))
      (node (ref "C10") (pin "2") (pinfunction "2_2") (pintype "passive"))
      (node (ref "C2") (pin "2") (pinfunction "2_2") (pintype "passive"))
      (node (ref "C3") (pin "2") (pinfunction "2_2") (pintype "passive"))
      (node (ref "C33") (pin "1") (pinfunction "1_1") (pintype "passive"))
      (node (ref "C34") (pin "2") (pinfunction "2_2") (pintype "passive"))
      (node (ref "C35") (pin "2") (pinfunction "2_2") (pintype "passive"))
      (node (ref "C36") (pin "2") (pinfunction "2_2") (pintype "passive"))
      (node (ref "C37") (pin "2") (pinfunction "2_2") (pintype "passive"))
      (node (ref "C38") (pin "2") (pinfunction "2_2") (pintype "passive"))
      (node (ref "C39") (pin "2") (pinfunction "2_2") (pintype "passive"))
      (node (ref "C4") (pin "2") (pinfunction "2_2") (pintype "passive"))
      (node (ref "C40") (pin "2") (pinfunction "2_2") (pintype "passive"))
      (node (ref "C41") (pin "2") (pinfunction "2_2") (pintype "passive"))
      (node (ref "C42") (pin "2") (pinfunction "2_2") (pintype "passive"))
      (node (ref "C43") (pin "2") (pinfunction "2_2") (pintype "passive"))
      (node (ref "C5") (pin "2") (pinfunction "2_2") (pintype "passive"))
      (node (ref "C6") (pin "2") (pinfunction "2_2") (pintype "passive"))
      (node (ref "C7") (pin "2") (pinfunction "2_2") (pintype "passive"))
      (node (ref "C8") (pin "2") (pinfunction "2_2") (pintype "passive"))
      (node (ref "C9") (pin "2") (pinfunction "2_2") (pintype "passive"))
      (node (ref "IC1") (pin "E11") (pinfunction "VDD_3_E11") (pintype "passive"))
      (node (ref "IC1") (pin "E6") (pinfunction "VDD_1_E6") (pintype "passive"))
      (node (ref "IC1") (pin "E9") (pinfunction "VDD_2_E9") (pintype "passive"))
      (node (ref "IC1") (pin "F5") (pinfunction "VDD_4_F5") (pintype "passive"))
      (node (ref "IC1") (pin "G13") (pinfunction "VDD_6_G13") (pintype "passive"))
      (node (ref "IC1") (pin "G5") (pinfunction "VDD_5_G5") (pintype "passive"))
      (node (ref "IC1") (pin "H13") (pinfunction "VDD_8_H13") (pintype "passive"))
      (node (ref "IC1") (pin "H5") (pinfunction "VDD_7_H5") (pintype "passive"))
      (node (ref "IC1") (pin "J13") (pinfunction "VDD_9_J13") (pintype "passive"))
      (node (ref "IC1") (pin "K13") (pinfunction "VDD_11_K13") (pintype "passive"))
      (node (ref "IC1") (pin "K5") (pinfunction "VDD_10_K5") (pintype "passive"))
      (node (ref "IC1") (pin "L13") (pinfunction "VDD_13_L13") (pintype "passive"))
      (node (ref "IC1") (pin "L5") (pinfunction "VDD_12_L5") (pintype "passive"))
      (node (ref "IC1") (pin "M13") (pinfunction "VDD_15_M13") (pintype "passive"))
      (node (ref "IC1") (pin "M5") (pinfunction "VDD_14_M5") (pintype "passive"))
      (node (ref "IC1") (pin "N10") (pinfunction "VDD_18_N10") (pintype "passive"))
      (node (ref "IC1") (pin "N11") (pinfunction "VDD_19_N11") (pintype "passive"))
      (node (ref "IC1") (pin "N12") (pinfunction "VDD_20_N12") (pintype "passive"))
      (node (ref "IC1") (pin "N7") (pinfunction "VDD_16_N7") (pintype "passive"))
      (node (ref "IC1") (pin "N8") (pinfunction "VDD_17_N8") (pintype "passive"))
      (node (ref "L1") (pin "1") (pinfunction "1_1") (pintype "passive"))
      (node (ref "L3") (pin "1") (pinfunction "1_1") (pintype "passive"))
      (node (ref "R3") (pin "1") (pinfunction "1_1") (pintype "passive"))
      (node (ref "SB13") (pin "1") (pinfunction "1_1") (pintype "passive"))
      (node (ref "SB14") (pin "1") (pinfunction "1_1") (pintype "passive"))
      (node (ref "SB15") (pin "2") (pinfunction "2_2") (pintype "passive"))
      (node (ref "SB3") (pin "2") (pinfunction "2_2") (pintype "passive"))
    )
    (net (code "25") (name "VDD_SDC") (class "Default")
      (node (ref "IC1") (pin "G2") (pinfunction "VFB_SMPS_G2") (pintype "passive"))
      (node (ref "L2") (pin "1") (pinfunction "1_1") (pintype "passive"))
      (node (ref "SB12") (pin "1") (pinfunction "1_1") (pintype "passive"))
      (node (ref "SB4") (pin "2") (pinfunction "2_2") (pintype "passive"))
      (node (ref "SB5") (pin "1") (pinfunction "1_1") (pintype "passive"))
    )
    (net (code "26") (name "VREF+") (class "Default")
      (node (ref "C15") (pin "2") (pinfunction "2_2") (pintype "passive"))
      (node (ref "C16") (pin "2") (pinfunction "2_2") (pintype "passive"))
      (node (ref "C18") (pin "2") (pinfunction "2_2") (pintype "passive"))
      (node (ref "IC1") (pin "M1") (pinfunction "VREF+_M1") (pintype "passive"))
      (node (ref "R6") (pin "1") (pinfunction "1_1") (pintype "passive"))
      (node (ref "U1") (pin "5") (pinfunction "OUT_S_5") (pintype "passive"))
      (node (ref "U1") (pin "6") (pinfunction "OUT_F_6") (pintype "passive"))
    )
    (net (code "27") (name "VREF-") (class "Default")
      (node (ref "IC1") (pin "N1") (pinfunction "VREF-_N1") (pintype "passive"))
      (node (ref "R5") (pin "1") (pinfunction "1_1") (pintype "passive"))
    )
    (net (code "28") (name "unconnected-(U2-NC-Pad1)") (class "Default")
      (node (ref "U2") (pin "1") (pinfunction "NC_1") (pintype "passive+no_connect"))
    )
    (net (code "29") (name "unconnected-(U2-NC-Pad4)") (class "Default")
      (node (ref "U2") (pin "4") (pinfunction "NC_4") (pintype "passive+no_connect"))
    )
    (net (code "30") (name "unconnected-(U2-NC-Pad5)") (class "Default")
      (node (ref "U2") (pin "5") (pinfunction "NC_5") (pintype "passive+no_connect"))
    )
  )
)
